# pc_heartypatch_v2.net
KiCad netlist of a schematic drawn in EAGLE
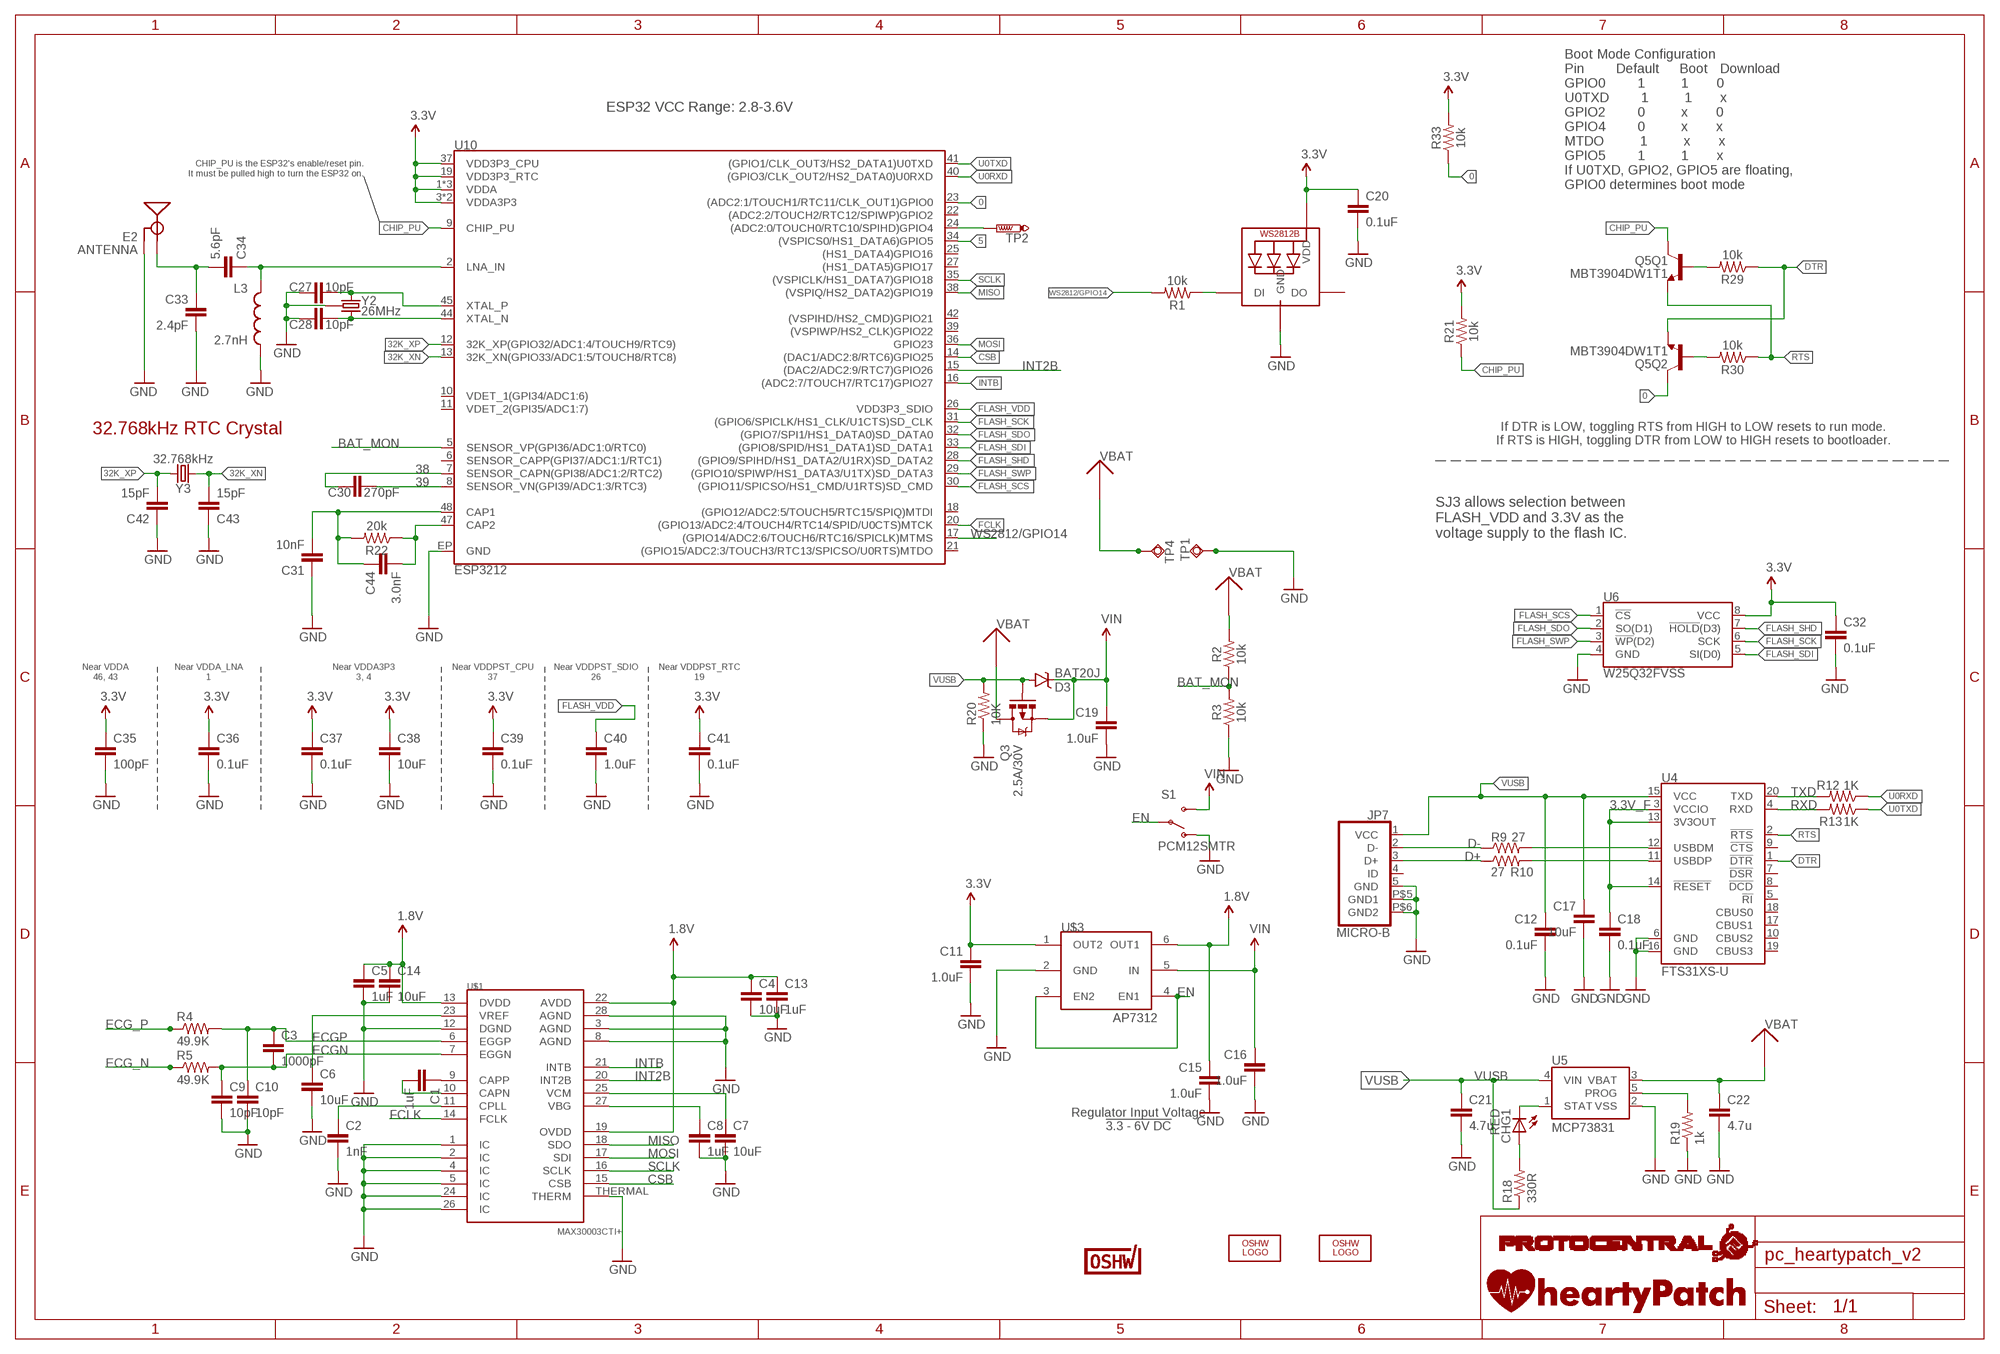
[diagram p0: schematic, sheet 1]

(export (version "E")
  (design (tool "Eeschema 10.0.6"))
  (components
    (comp (ref "C1")
      (value "1uF")
      (footprint "eagle-import:C0603")
      (libsource (lib "eagle-import") (part "C-EUC0603"))
    )
    (comp (ref "C2")
      (value "1nF")
      (footprint "eagle-import:C0603")
      (libsource (lib "eagle-import") (part "C-EUC0603"))
    )
    (comp (ref "C3")
      (value "1000pF")
      (footprint "eagle-import:C0402")
      (libsource (lib "eagle-import") (part "C-EUC0402"))
    )
    (comp (ref "C4")
      (value "10uF")
      (footprint "eagle-import:C0805")
      (libsource (lib "eagle-import") (part "C-EUC0805"))
    )
    (comp (ref "C5")
      (value "1uF")
      (footprint "eagle-import:C0402")
      (libsource (lib "eagle-import") (part "C-EUC0402"))
    )
    (comp (ref "C6")
      (value "10uF")
      (footprint "eagle-import:C0805")
      (libsource (lib "eagle-import") (part "C-EUC0805"))
    )
    (comp (ref "C7")
      (value "10uF")
      (footprint "eagle-import:C0805")
      (libsource (lib "eagle-import") (part "C-EUC0805"))
    )
    (comp (ref "C8")
      (value "1uF")
      (footprint "eagle-import:C0805")
      (libsource (lib "eagle-import") (part "C-EUC0805"))
    )
    (comp (ref "C9")
      (value "10pF")
      (footprint "eagle-import:C0402")
      (libsource (lib "eagle-import") (part "C-EUC0402"))
    )
    (comp (ref "C10")
      (value "10pF")
      (footprint "eagle-import:C0402")
      (libsource (lib "eagle-import") (part "C-EUC0402"))
    )
    (comp (ref "C11")
      (value "1.0uF")
      (footprint "eagle-import:0805")
      (libsource (lib "eagle-import") (part "1.0UF-0805-25V-10%"))
    )
    (comp (ref "C12")
      (value "0.1uF")
      (footprint "eagle-import:C0402")
      (libsource (lib "eagle-import") (part "C-EUC0402"))
    )
    (comp (ref "C13")
      (value "1uF")
      (footprint "eagle-import:C0805")
      (libsource (lib "eagle-import") (part "C-EUC0805"))
    )
    (comp (ref "C14")
      (value "10uF")
      (footprint "eagle-import:C0603")
      (libsource (lib "eagle-import") (part "C-EUC0603"))
    )
    (comp (ref "C15")
      (value "1.0uF")
      (footprint "eagle-import:0805")
      (libsource (lib "eagle-import") (part "1.0UF-0805-25V-10%"))
    )
    (comp (ref "C16")
      (value "1.0uF")
      (footprint "eagle-import:0805")
      (libsource (lib "eagle-import") (part "1.0UF-0805-25V-10%"))
    )
    (comp (ref "C17")
      (value "10uF")
      (footprint "eagle-import:C0805")
      (libsource (lib "eagle-import") (part "C-EUC0805"))
    )
    (comp (ref "C18")
      (value "0.1uF")
      (footprint "eagle-import:C0402")
      (libsource (lib "eagle-import") (part "C-EUC0402"))
    )
    (comp (ref "C19")
      (value "1.0uF")
      (footprint "eagle-import:C0402")
      (libsource (lib "eagle-import") (part "C-EUC0402"))
    )
    (comp (ref "C20")
      (value "0.1uF")
      (footprint "eagle-import:0603")
      (libsource (lib "eagle-import") (part "0.1UF-0603-25V-(+80/-20%)"))
    )
    (comp (ref "C21")
      (value "4.7u")
      (footprint "eagle-import:C0805")
      (libsource (lib "eagle-import") (part "C-EUC0805"))
    )
    (comp (ref "C22")
      (value "4.7u")
      (footprint "eagle-import:C0805")
      (libsource (lib "eagle-import") (part "C-EUC0805"))
    )
    (comp (ref "C27")
      (value "10pF")
      (footprint "eagle-import:0603")
      (libsource (lib "eagle-import") (part "10PF-0603-50V-5%"))
    )
    (comp (ref "C28")
      (value "10pF")
      (footprint "eagle-import:0603")
      (libsource (lib "eagle-import") (part "10PF-0603-50V-5%"))
    )
    (comp (ref "C30")
      (value "270pF")
      (footprint "eagle-import:0603")
      (libsource (lib "eagle-import") (part "270PF-50V-5%(0603)"))
    )
    (comp (ref "C31")
      (value "10nF")
      (footprint "eagle-import:0603")
      (libsource (lib "eagle-import") (part "10NF-0603-50V-10%"))
    )
    (comp (ref "C32")
      (value "0.1uF")
      (footprint "eagle-import:0402")
      (libsource (lib "eagle-import") (part "0.1UF-0402-16V-10%"))
    )
    (comp (ref "C33")
      (value "2.4pF")
      (footprint "eagle-import:0603")
      (libsource (lib "eagle-import") (part "2.4PF-0603-50V-5%"))
    )
    (comp (ref "C34")
      (value "5.6pF")
      (footprint "eagle-import:0603")
      (libsource (lib "eagle-import") (part "5.6PF-50V-5%(0603)"))
    )
    (comp (ref "C35")
      (value "100pF")
      (footprint "eagle-import:0603")
      (libsource (lib "eagle-import") (part "100PF-0603-50V-5%"))
    )
    (comp (ref "C36")
      (value "0.1uF")
      (footprint "eagle-import:0603")
      (libsource (lib "eagle-import") (part "0.1UF-0603-25V-(+80/-20%)"))
    )
    (comp (ref "C37")
      (value "0.1uF")
      (footprint "eagle-import:0603")
      (libsource (lib "eagle-import") (part "0.1UF-0603-25V-(+80/-20%)"))
    )
    (comp (ref "C38")
      (value "10uF")
      (footprint "eagle-import:0603")
      (libsource (lib "eagle-import") (part "10UF-0603-6.3V-20%"))
    )
    (comp (ref "C39")
      (value "0.1uF")
      (footprint "eagle-import:0402")
      (libsource (lib "eagle-import") (part "0.1UF-0402-16V-10%"))
    )
    (comp (ref "C40")
      (value "1.0uF")
      (footprint "eagle-import:0603")
      (libsource (lib "eagle-import") (part "1.0UF-0603-16V-10%"))
    )
    (comp (ref "C41")
      (value "0.1uF")
      (footprint "eagle-import:0603")
      (libsource (lib "eagle-import") (part "0.1UF-0603-25V-(+80/-20%)"))
    )
    (comp (ref "C42")
      (value "15pF")
      (footprint "eagle-import:0603")
      (libsource (lib "eagle-import") (part "15PF-0603-50V-5%"))
    )
    (comp (ref "C43")
      (value "15pF")
      (footprint "eagle-import:0603")
      (libsource (lib "eagle-import") (part "15PF-0603-50V-5%"))
    )
    (comp (ref "C44")
      (value "3.0nF")
      (footprint "eagle-import:0603")
      (libsource (lib "eagle-import") (part "3.0NF-0603-50V-5%"))
    )
    (comp (ref "CHG1")
      (value "RED")
      (footprint "eagle-import:CHIPLED_0603")
      (libsource (lib "eagle-import") (part "LEDCHIPLED_0603"))
    )
    (comp (ref "D3")
      (value "BAT20J")
      (footprint "eagle-import:SOD-323")
      (libsource (lib "eagle-import") (part "DIODE-SCHOTTKY-BAT20J"))
    )
    (comp (ref "E2")
      (value "ANTENNA")
      (footprint "eagle-import:TRACE_ANTENNA_2.4GHZ_25.7MM_TUNED")
      (libsource (lib "eagle-import") (part "ANTENNATRACE-TUNED"))
    )
    (comp (ref "JP7")
      (value "MICRO-B")
      (footprint "eagle-import:MICRO-B")
      (libsource (lib "eagle-import") (part "MICRO-B"))
    )
    (comp (ref "L3")
      (value "2.7nH")
      (footprint "eagle-import:0603")
      (libsource (lib "eagle-import") (part "INDUCTOR0603"))
    )
    (comp (ref "LED1")
      (value "WS2812B5050")
      (footprint "eagle-import:WS2812B")
      (libsource (lib "eagle-import") (part "WS2812B5050"))
    )
    (comp (ref "LOGO1")
      (value "OSHW_LOGO_FILLX0200-NT")
      (footprint "eagle-import:OSHW_FILLX200_NOTEXT")
      (libsource (lib "eagle-import") (part "OSHW_LOGO_FILLX0200-NT"))
    )
    (comp (ref "LOGO2")
      (value "OSHW_LOGO_FILLX0200-NT")
      (footprint "eagle-import:OSHW_FILLX200_NOTEXT")
      (libsource (lib "eagle-import") (part "OSHW_LOGO_FILLX0200-NT"))
    )
    (comp (ref "Q3")
      (value "2.5A/30V")
      (footprint "eagle-import:SOT23-3")
      (libsource (lib "eagle-import") (part "MOSFET-PCHANNELDMG2307L"))
    )
    (comp (ref "Q5")
      (value "MBT3904DW1T1")
      (footprint "eagle-import:SC70-6")
      (libsource (lib "eagle-import") (part "MBT3904DW1T1"))
    )
    (comp (ref "R1")
      (value "10k")
      (footprint "eagle-import:0603")
      (libsource (lib "eagle-import") (part "10KOHM-1/10W-1%(0603)0603"))
    )
    (comp (ref "R2")
      (value "10k")
      (footprint "eagle-import:0603")
      (libsource (lib "eagle-import") (part "10KOHM-1/10W-1%(0603)0603"))
    )
    (comp (ref "R3")
      (value "10k")
      (footprint "eagle-import:0603")
      (libsource (lib "eagle-import") (part "10KOHM-1/10W-1%(0603)0603"))
    )
    (comp (ref "R4")
      (value "49.9K")
      (footprint "eagle-import:0805")
      (libsource (lib "eagle-import") (part "RESISTOR0805-RES"))
    )
    (comp (ref "R5")
      (value "49.9K")
      (footprint "eagle-import:0805")
      (libsource (lib "eagle-import") (part "RESISTOR0805-RES"))
    )
    (comp (ref "R9")
      (value "27")
      (footprint "eagle-import:R0402")
      (libsource (lib "eagle-import") (part "R-US_R0402"))
    )
    (comp (ref "R10")
      (value "27")
      (footprint "eagle-import:R0402")
      (libsource (lib "eagle-import") (part "R-US_R0402"))
    )
    (comp (ref "R12")
      (value "1K")
      (footprint "eagle-import:R0402")
      (libsource (lib "eagle-import") (part "R-US_R0402"))
    )
    (comp (ref "R13")
      (value "1K")
      (footprint "eagle-import:R0402")
      (libsource (lib "eagle-import") (part "R-US_R0402"))
    )
    (comp (ref "R18")
      (value "330R")
      (footprint "eagle-import:R0402")
      (libsource (lib "eagle-import") (part "R-US_R0402"))
    )
    (comp (ref "R19")
      (value "1k")
      (footprint "eagle-import:R0402")
      (libsource (lib "eagle-import") (part "R-US_R0402"))
    )
    (comp (ref "R20")
      (value "10K")
      (footprint "eagle-import:R0402")
      (libsource (lib "eagle-import") (part "R-US_R0402"))
    )
    (comp (ref "R21")
      (value "10k")
      (footprint "eagle-import:0603")
      (libsource (lib "eagle-import") (part "10KOHM-1/10W-1%(0603)0603"))
    )
    (comp (ref "R22")
      (value "20k")
      (footprint "eagle-import:0603")
      (libsource (lib "eagle-import") (part "20KOHM-0603-1/10W-1%"))
    )
    (comp (ref "R29")
      (value "10k")
      (footprint "eagle-import:0603")
      (libsource (lib "eagle-import") (part "10KOHM-0603-1/10W-1%"))
    )
    (comp (ref "R30")
      (value "10k")
      (footprint "eagle-import:0603")
      (libsource (lib "eagle-import") (part "10KOHM-0603-1/10W-1%"))
    )
    (comp (ref "R33")
      (value "10k")
      (footprint "eagle-import:0603")
      (libsource (lib "eagle-import") (part "10KOHM-1/10W-1%(0603)0603"))
    )
    (comp (ref "S1")
      (value "PCM12SMTR")
      (footprint "eagle-import:SWITCH-SPST-SMD-A")
      (libsource (lib "eagle-import") (part "SWITCH-SPDT-SMD-A"))
    )
    (comp (ref "TP1")
      (value "TPSQTP20SQ")
      (footprint "eagle-import:TP20SQ")
      (libsource (lib "eagle-import") (part "TPSQTP20SQ"))
    )
    (comp (ref "TP2")
      (value "PTR1TP10SQ")
      (footprint "eagle-import:TP10SQ")
      (libsource (lib "eagle-import") (part "PTR1TP10SQ"))
    )
    (comp (ref "TP4")
      (value "TPSQTP20SQ")
      (footprint "eagle-import:TP20SQ")
      (libsource (lib "eagle-import") (part "TPSQTP20SQ"))
    )
    (comp (ref "U$1")
      (value "MAX30003CTI+")
      (footprint "eagle-import:QFN-28")
      (libsource (lib "eagle-import") (part "MAX30003"))
    )
    (comp (ref "U$3")
      (value "AP7312")
      (footprint "eagle-import:SOT26")
      (libsource (lib "eagle-import") (part "AP7312"))
    )
    (comp (ref "U$8")
      (value "HEARTYPATCHHEART")
      (footprint "eagle-import:HEARTYPATCH")
      (libsource (lib "eagle-import") (part "HEARTYPATCHHEART"))
    )
    (comp (ref "U$9")
      (value "PROTY_LOGO_WITH_TEXT")
      (footprint "eagle-import:PROTY_WITH_TEXT")
      (libsource (lib "eagle-import") (part "PROTY_LOGO_WITH_TEXT"))
    )
    (comp (ref "U$10")
      (value "CERT-SMALL")
      (footprint "eagle-import:CERT-SMALL-SILK")
      (libsource (lib "eagle-import") (part "CERT-SMALL"))
    )
    (comp (ref "U4")
      (value "FTS31XS-U")
      (footprint "eagle-import:SSOP20_L")
      (libsource (lib "eagle-import") (part "FT231XS"))
    )
    (comp (ref "U5")
      (value "MCP73831")
      (footprint "eagle-import:SOT23-5")
      (libsource (lib "eagle-import") (part "MCP73831"))
    )
    (comp (ref "U6")
      (value "W25Q32FVSS")
      (footprint "eagle-import:SOIC-8")
      (libsource (lib "eagle-import") (part "W25Q32FVSS"))
    )
    (comp (ref "U10")
      (value "ESP3212")
      (footprint "eagle-import:QFN48-0.4MM")
      (libsource (lib "eagle-import") (part "ESP3212"))
    )
    (comp (ref "Y2")
      (value "26MHz")
      (footprint "eagle-import:CRYSTAL-SMD-3.2X2.5")
      (libsource (lib "eagle-import") (part "CRYSTAL-GROUNDED3.2X2.5"))
    )
    (comp (ref "Y3")
      (value "32.768kHz")
      (footprint "eagle-import:CRYSTAL-SMD-3.2X1.5MM")
      (libsource (lib "eagle-import") (part "CRYSTAL-32.768KHZSMD-3.2X1.5"))
    )
  )
  (nets
    (net (code "1") (name "/3.3V_F") (class "Default")
      (node (ref "C18") (pin "1") (pinfunction "1_1") (pintype "passive"))
      (node (ref "U4") (pin "13") (pinfunction "3V3OUT_13") (pintype "bidirectional"))
      (node (ref "U4") (pin "14") (pinfunction "~{RESET}_14") (pintype "bidirectional"))
      (node (ref "U4") (pin "3") (pinfunction "VCCIO_3") (pintype "bidirectional"))
    )
    (net (code "2") (name "/38") (class "Default")
      (node (ref "C30") (pin "1") (pinfunction "1_1") (pintype "passive"))
      (node (ref "U10") (pin "7") (pinfunction "SENSOR_CAPN(GPI38/ADC1:2/RTC2)_7") (pintype "bidirectional"))
    )
    (net (code "3") (name "/39") (class "Default")
      (node (ref "C30") (pin "2") (pinfunction "2_2") (pintype "passive"))
      (node (ref "U10") (pin "8") (pinfunction "SENSOR_VN(GPI39/ADC1:3/RTC3)_8") (pintype "bidirectional"))
    )
    (net (code "4") (name "/BAT_MON") (class "Default")
      (node (ref "R2") (pin "1") (pinfunction "1_1") (pintype "passive"))
      (node (ref "R3") (pin "2") (pinfunction "2_2") (pintype "passive"))
      (node (ref "U10") (pin "5") (pinfunction "SENSOR_VP(GPI36/ADC1:0/RTC0)_5") (pintype "bidirectional"))
    )
    (net (code "5") (name "/D+") (class "Default")
      (node (ref "JP7") (pin "3") (pinfunction "D+_3") (pintype "bidirectional"))
      (node (ref "R10") (pin "1") (pinfunction "1_1") (pintype "passive"))
    )
    (net (code "6") (name "/D-") (class "Default")
      (node (ref "JP7") (pin "2") (pinfunction "D-_2") (pintype "bidirectional"))
      (node (ref "R9") (pin "1") (pinfunction "1_1") (pintype "passive"))
    )
    (net (code "7") (name "/ECGN") (class "Default")
      (node (ref "C3") (pin "2") (pinfunction "2_2") (pintype "passive"))
      (node (ref "C9") (pin "1") (pinfunction "1_1") (pintype "passive"))
      (node (ref "R5") (pin "2") (pinfunction "2_2") (pintype "passive"))
      (node (ref "U$1") (pin "7") (pinfunction "EGGN_7") (pintype "bidirectional"))
    )
    (net (code "8") (name "/ECGP") (class "Default")
      (node (ref "C10") (pin "1") (pinfunction "1_1") (pintype "passive"))
      (node (ref "C3") (pin "1") (pinfunction "1_1") (pintype "passive"))
      (node (ref "R4") (pin "2") (pinfunction "2_2") (pintype "passive"))
      (node (ref "U$1") (pin "6") (pinfunction "EGGP_6") (pintype "bidirectional"))
    )
    (net (code "9") (name "/ECG_N") (class "Default")
      (node (ref "R5") (pin "1") (pinfunction "1_1") (pintype "passive"))
    )
    (net (code "10") (name "/ECG_P") (class "Default")
      (node (ref "R4") (pin "1") (pinfunction "1_1") (pintype "passive"))
    )
    (net (code "11") (name "/EN") (class "Default")
      (node (ref "S1") (pin "2") (pinfunction "P_2") (pintype "passive"))
      (node (ref "U$3") (pin "3") (pinfunction "EN2_3") (pintype "bidirectional"))
      (node (ref "U$3") (pin "4") (pinfunction "EN1_4") (pintype "bidirectional"))
    )
    (net (code "12") (name "/INT2B") (class "Default")
      (node (ref "U$1") (pin "20") (pinfunction "INT2B_20") (pintype "bidirectional"))
      (node (ref "U10") (pin "15") (pinfunction "(DAC2/ADC2:9/RTC7)GPIO26_15") (pintype "bidirectional"))
    )
    (net (code "13") (name "/RXD") (class "Default")
      (node (ref "R13") (pin "2") (pinfunction "2_2") (pintype "passive"))
      (node (ref "U4") (pin "4") (pinfunction "RXD_4") (pintype "bidirectional"))
    )
    (net (code "14") (name "/TXD") (class "Default")
      (node (ref "R12") (pin "2") (pinfunction "2_2") (pintype "passive"))
      (node (ref "U4") (pin "20") (pinfunction "TXD_20") (pintype "bidirectional"))
    )
    (net (code "15") (name "0") (class "Default")
      (node (ref "Q5") (pin "6") (pinfunction "C_6") (pintype "passive"))
      (node (ref "R33") (pin "1") (pinfunction "1_1") (pintype "passive"))
      (node (ref "U10") (pin "23") (pinfunction "(ADC2:1/TOUCH1/RTC11/CLK_OUT1)GPIO0_23") (pintype "bidirectional"))
    )
    (net (code "16") (name "1.8V") (class "Default")
      (node (ref "C13") (pin "1") (pinfunction "1_1") (pintype "passive"))
      (node (ref "C14") (pin "1") (pinfunction "1_1") (pintype "passive"))
      (node (ref "C15") (pin "1") (pinfunction "1_1") (pintype "passive"))
      (node (ref "C4") (pin "1") (pinfunction "1_1") (pintype "passive"))
      (node (ref "C5") (pin "1") (pinfunction "1_1") (pintype "passive"))
      (node (ref "U$1") (pin "13") (pinfunction "DVDD_13") (pintype "bidirectional"))
      (node (ref "U$1") (pin "19") (pinfunction "OVDD_19") (pintype "bidirectional"))
      (node (ref "U$1") (pin "22") (pinfunction "AVDD_22") (pintype "bidirectional"))
      (node (ref "U$3") (pin "6") (pinfunction "OUT1_6") (pintype "bidirectional"))
    )
    (net (code "17") (name "3.3V") (class "Default")
      (node (ref "C11") (pin "1") (pinfunction "1_1") (pintype "passive"))
      (node (ref "C20") (pin "1") (pinfunction "1_1") (pintype "passive"))
      (node (ref "C32") (pin "1") (pinfunction "1_1") (pintype "passive"))
      (node (ref "C35") (pin "1") (pinfunction "1_1") (pintype "passive"))
      (node (ref "C36") (pin "1") (pinfunction "1_1") (pintype "passive"))
      (node (ref "C37") (pin "1") (pinfunction "1_1") (pintype "passive"))
      (node (ref "C38") (pin "1") (pinfunction "1_1") (pintype "passive"))
      (node (ref "C39") (pin "1") (pinfunction "1_1") (pintype "passive"))
      (node (ref "C41") (pin "1") (pinfunction "1_1") (pintype "passive"))
      (node (ref "LED1") (pin "1-VDD") (pinfunction "VDD_1-VDD") (pintype "power_in"))
      (node (ref "R21") (pin "2") (pinfunction "2_2") (pintype "passive"))
      (node (ref "R33") (pin "2") (pinfunction "2_2") (pintype "passive"))
      (node (ref "U$3") (pin "1") (pinfunction "OUT2_1") (pintype "bidirectional"))
      (node (ref "U10") (pin "1") (pinfunction "VDDA_1") (pintype "bidirectional"))
      (node (ref "U10") (pin "19") (pinfunction "VDD3P3_RTC_19") (pintype "bidirectional"))
      (node (ref "U10") (pin "3") (pinfunction "VDDA3P3_3") (pintype "bidirectional"))
      (node (ref "U10") (pin "37") (pinfunction "VDD3P3_CPU_37") (pintype "bidirectional"))
      (node (ref "U10") (pin "4") (pinfunction "VDDA3P3_4") (pintype "bidirectional"))
      (node (ref "U10") (pin "43") (pinfunction "VDDA_43") (pintype "bidirectional"))
      (node (ref "U10") (pin "46") (pinfunction "VDDA_46") (pintype "bidirectional"))
      (node (ref "U6") (pin "8") (pinfunction "VCC_8") (pintype "bidirectional"))
    )
    (net (code "18") (name "5") (class "Default")
      (node (ref "U10") (pin "34") (pinfunction "(VSPICS0/HS1_DATA6)GPIO5_34") (pintype "bidirectional"))
    )
    (net (code "19") (name "32K_XN") (class "Default")
      (node (ref "C43") (pin "2") (pinfunction "2_2") (pintype "passive"))
      (node (ref "U10") (pin "13") (pinfunction "32K_XN(GPIO33/ADC1:5/TOUCH8/RTC8)_13") (pintype "bidirectional"))
      (node (ref "Y3") (pin "P$2") (pinfunction "2_P$2") (pintype "passive"))
    )
    (net (code "20") (name "32K_XP") (class "Default")
      (node (ref "C42") (pin "2") (pinfunction "2_2") (pintype "passive"))
      (node (ref "U10") (pin "12") (pinfunction "32K_XP(GPIO32/ADC1:4/TOUCH9/RTC9)_12") (pintype "bidirectional"))
      (node (ref "Y3") (pin "P$1") (pinfunction "1_P$1") (pintype "passive"))
    )
    (net (code "21") (name "CHIP_PU") (class "Default")
      (node (ref "Q5") (pin "3") (pinfunction "C_3") (pintype "passive"))
      (node (ref "R21") (pin "1") (pinfunction "1_1") (pintype "passive"))
      (node (ref "U10") (pin "9") (pinfunction "CHIP_PU_9") (pintype "bidirectional"))
    )
    (net (code "22") (name "CSB") (class "Default")
      (node (ref "U$1") (pin "15") (pinfunction "CSB_15") (pintype "bidirectional"))
      (node (ref "U10") (pin "14") (pinfunction "(DAC1/ADC2:8/RTC6)GPIO25_14") (pintype "bidirectional"))
    )
    (net (code "23") (name "DTR") (class "Default")
      (node (ref "Q5") (pin "1") (pinfunction "E_1") (pintype "passive"))
      (node (ref "R29") (pin "1") (pinfunction "1_1") (pintype "passive"))
      (node (ref "U4") (pin "1") (pinfunction "~{DTR}_1") (pintype "bidirectional"))
    )
    (net (code "24") (name "FCLK") (class "Default")
      (node (ref "U$1") (pin "14") (pinfunction "FCLK_14") (pintype "bidirectional"))
      (node (ref "U10") (pin "20") (pinfunction "(GPIO13/ADC2:4/TOUCH4/RTC14/SPID/U0CTS)MTCK_20") (pintype "bidirectional"))
    )
    (net (code "25") (name "FLASH_SCK") (class "Default")
      (node (ref "U10") (pin "31") (pinfunction "(GPIO6/SPICLK/HS1_CLK/U1CTS)SD_CLK_31") (pintype "bidirectional"))
      (node (ref "U6") (pin "6") (pinfunction "SCK_6") (pintype "bidirectional"))
    )
    (net (code "26") (name "FLASH_SCS") (class "Default")
      (node (ref "U10") (pin "30") (pinfunction "(GPIO11/SPICSO/HS1_CMD/U1RTS)SD_CMD_30") (pintype "bidirectional"))
      (node (ref "U6") (pin "1") (pinfunction "~{CS}_1") (pintype "bidirectional"))
    )
    (net (code "27") (name "FLASH_SDI") (class "Default")
      (node (ref "U10") (pin "33") (pinfunction "(GPIO8/SPID/HS1_DATA1)SD_DATA1_33") (pintype "bidirectional"))
      (node (ref "U6") (pin "5") (pinfunction "SI(D0)_5") (pintype "bidirectional"))
    )
    (net (code "28") (name "FLASH_SDO") (class "Default")
      (node (ref "U10") (pin "32") (pinfunction "(GPIO7/SPI1/HS1_DATA0)SD_DATA0_32") (pintype "bidirectional"))
      (node (ref "U6") (pin "2") (pinfunction "SO(D1)_2") (pintype "bidirectional"))
    )
    (net (code "29") (name "FLASH_SHD") (class "Default")
      (node (ref "U10") (pin "28") (pinfunction "(GPIO9/SPIHD/HS1_DATA2/U1RX)SD_DATA2_28") (pintype "bidirectional"))
      (node (ref "U6") (pin "7") (pinfunction "~{HOLD}(D3)_7") (pintype "bidirectional"))
    )
    (net (code "30") (name "FLASH_SWP") (class "Default")
      (node (ref "U10") (pin "29") (pinfunction "(GPIO10/SPIWP/HS1_DATA3/U1TX)SD_DATA3_29") (pintype "bidirectional"))
      (node (ref "U6") (pin "3") (pinfunction "~{WP}(D2)_3") (pintype "bidirectional"))
    )
    (net (code "31") (name "FLASH_VDD") (class "Default")
      (node (ref "C40") (pin "1") (pinfunction "1_1") (pintype "passive"))
      (node (ref "U10") (pin "26") (pinfunction "VDD3P3_SDIO_26") (pintype "bidirectional"))
    )
    (net (code "32") (name "GND") (class "Default")
      (node (ref "C10") (pin "2") (pinfunction "2_2") (pintype "passive"))
      (node (ref "C11") (pin "2") (pinfunction "2_2") (pintype "passive"))
      (node (ref "C12") (pin "2") (pinfunction "2_2") (pintype "passive"))
      (node (ref "C13") (pin "2") (pinfunction "2_2") (pintype "passive"))
      (node (ref "C14") (pin "2") (pinfunction "2_2") (pintype "passive"))
      (node (ref "C15") (pin "2") (pinfunction "2_2") (pintype "passive"))
      (node (ref "C16") (pin "2") (pinfunction "2_2") (pintype "passive"))
      (node (ref "C17") (pin "2") (pinfunction "2_2") (pintype "passive"))
      (node (ref "C18") (pin "2") (pinfunction "2_2") (pintype "passive"))
      (node (ref "C19") (pin "2") (pinfunction "2_2") (pintype "passive"))
      (node (ref "C2") (pin "2") (pinfunction "2_2") (pintype "passive"))
      (node (ref "C20") (pin "2") (pinfunction "2_2") (pintype "passive"))
      (node (ref "C21") (pin "2") (pinfunction "2_2") (pintype "passive"))
      (node (ref "C22") (pin "2") (pinfunction "2_2") (pintype "passive"))
      (node (ref "C27") (pin "1") (pinfunction "1_1") (pintype "passive"))
      (node (ref "C28") (pin "1") (pinfunction "1_1") (pintype "passive"))
      (node (ref "C31") (pin "1") (pinfunction "1_1") (pintype "passive"))
      (node (ref "C32") (pin "2") (pinfunction "2_2") (pintype "passive"))
      (node (ref "C33") (pin "2") (pinfunction "2_2") (pintype "passive"))
      (node (ref "C35") (pin "2") (pinfunction "2_2") (pintype "passive"))
      (node (ref "C36") (pin "2") (pinfunction "2_2") (pintype "passive"))
      (node (ref "C37") (pin "2") (pinfunction "2_2") (pintype "passive"))
      (node (ref "C38") (pin "2") (pinfunction "2_2") (pintype "passive"))
      (node (ref "C39") (pin "2") (pinfunction "2_2") (pintype "passive"))
      (node (ref "C4") (pin "2") (pinfunction "2_2") (pintype "passive"))
      (node (ref "C40") (pin "2") (pinfunction "2_2") (pintype "passive"))
      (node (ref "C41") (pin "2") (pinfunction "2_2") (pintype "passive"))
      (node (ref "C42") (pin "1") (pinfunction "1_1") (pintype "passive"))
      (node (ref "C43") (pin "1") (pinfunction "1_1") (pintype "passive"))
      (node (ref "C5") (pin "2") (pinfunction "2_2") (pintype "passive"))
      (node (ref "C6") (pin "2") (pinfunction "2_2") (pintype "passive"))
      (node (ref "C7") (pin "2") (pinfunction "2_2") (pintype "passive"))
      (node (ref "C8") (pin "2") (pinfunction "2_2") (pintype "passive"))
      (node (ref "C9") (pin "2") (pinfunction "2_2") (pintype "passive"))
      (node (ref "E2") (pin "GND") (pinfunction "GND_GND") (pintype "bidirectional"))
      (node (ref "E2") (pin "GND2") (pinfunction "GND_GND2") (pintype "bidirectional"))
      (node (ref "JP7") (pin "5") (pinfunction "GND_5") (pintype "bidirectional"))
      (node (ref "JP7") (pin "P$5") (pinfunction "GND1_P$5") (pintype "bidirectional"))
      (node (ref "JP7") (pin "P$6") (pinfunction "GND2_P$6") (pintype "bidirectional"))
      (node (ref "L3") (pin "2") (pinfunction "2_2") (pintype "passive"))
      (node (ref "LED1") (pin "3-GND") (pinfunction "GND_3-GND") (pintype "power_in"))
      (node (ref "R19") (pin "1") (pinfunction "1_1") (pintype "passive"))
      (node (ref "R20") (pin "1") (pinfunction "1_1") (pintype "passive"))
      (node (ref "R3") (pin "1") (pinfunction "1_1") (pintype "passive"))
      (node (ref "S1") (pin "1") (pinfunction "O_1") (pintype "passive"))
      (node (ref "TP1") (pin "TP") (pinfunction "TP_TP") (pintype "input"))
      (node (ref "U$1") (pin "1") (pinfunction "IC_1") (pintype "bidirectional"))
      (node (ref "U$1") (pin "12") (pinfunction "DGND_12") (pintype "bidirectional"))
      (node (ref "U$1") (pin "2") (pinfunction "IC_2") (pintype "bidirectional"))
      (node (ref "U$1") (pin "24") (pinfunction "IC_24") (pintype "bidirectional"))
      (node (ref "U$1") (pin "26") (pinfunction "IC_26") (pintype "bidirectional"))
      (node (ref "U$1") (pin "28") (pinfunction "AGND_28") (pintype "bidirectional"))
      (node (ref "U$1") (pin "3") (pinfunction "AGND_3") (pintype "bidirectional"))
      (node (ref "U$1") (pin "4") (pinfunction "IC_4") (pintype "bidirectional"))
      (node (ref "U$1") (pin "5") (pinfunction "IC_5") (pintype "bidirectional"))
      (node (ref "U$1") (pin "8") (pinfunction "AGND_8") (pintype "bidirectional"))
      (node (ref "U$1") (pin "THERMAL") (pinfunction "THERM_THERMAL") (pintype "bidirectional"))
      (node (ref "U$3") (pin "2") (pinfunction "GND_2") (pintype "bidirectional"))
      (node (ref "U10") (pin "EP") (pinfunction "GND_EP") (pintype "bidirectional"))
      (node (ref "U4") (pin "16") (pinfunction "GND_16") (pintype "bidirectional"))
      (node (ref "U4") (pin "6") (pinfunction "GND_6") (pintype "bidirectional"))
      (node (ref "U5") (pin "2") (pinfunction "VSS_2") (pintype "power_in"))
      (node (ref "U6") (pin "4") (pinfunction "GND_4") (pintype "bidirectional"))
      (node (ref "Y2") (pin "2") (pinfunction "GND_2") (pintype "passive"))
      (node (ref "Y2") (pin "4") (pinfunction "GND_4") (pintype "passive"))
    )
    (net (code "33") (name "INTB") (class "Default")
      (node (ref "U$1") (pin "21") (pinfunction "INTB_21") (pintype "bidirectional"))
      (node (ref "U10") (pin "16") (pinfunction "(ADC2:7/TOUCH7/RTC17)GPIO27_16") (pintype "bidirectional"))
    )
    (net (code "34") (name "MISO") (class "Default")
      (node (ref "U$1") (pin "18") (pinfunction "SDO_18") (pintype "bidirectional"))
      (node (ref "U10") (pin "38") (pinfunction "(VSPIQ/HS2_DATA2)GPIO19_38") (pintype "bidirectional"))
    )
    (net (code "35") (name "MOSI") (class "Default")
      (node (ref "U$1") (pin "17") (pinfunction "SDI_17") (pintype "bidirectional"))
      (node (ref "U10") (pin "36") (pinfunction "GPIO23_36") (pintype "bidirectional"))
    )
    (net (code "36") (name "Net-(CHG1-PadA)") (class "Default")
      (node (ref "CHG1") (pin "A") (pinfunction "A_A") (pintype "passive"))
      (node (ref "R18") (pin "2") (pinfunction "2_2") (pintype "passive"))
    )
    (net (code "37") (name "Net-(E2-SIGNAL)") (class "Default")
      (node (ref "C33") (pin "1") (pinfunction "1_1") (pintype "passive"))
      (node (ref "C34") (pin "2") (pinfunction "2_2") (pintype "passive"))
      (node (ref "E2") (pin "ANT") (pinfunction "SIGNAL_ANT") (pintype "bidirectional"))
    )
    (net (code "38") (name "Net-(LED1-DI)") (class "Default")
      (node (ref "LED1") (pin "4-DIN") (pinfunction "DI_4-DIN") (pintype "input"))
      (node (ref "R1") (pin "1") (pinfunction "1_1") (pintype "passive"))
    )
    (net (code "39") (name "Net-(Q5A-B)") (class "Default")
      (node (ref "Q5") (pin "5") (pinfunction "B_5") (pintype "passive"))
      (node (ref "R29") (pin "2") (pinfunction "2_2") (pintype "passive"))
    )
    (net (code "40") (name "Net-(Q5B-B)") (class "Default")
      (node (ref "Q5") (pin "2") (pinfunction "B_2") (pintype "passive"))
      (node (ref "R30") (pin "2") (pinfunction "2_2") (pintype "passive"))
    )
    (net (code "41") (name "Net-(U$1-CAPN)") (class "Default")
      (node (ref "C1") (pin "2") (pinfunction "2_2") (pintype "passive"))
      (node (ref "U$1") (pin "10") (pinfunction "CAPN_10") (pintype "bidirectional"))
    )
    (net (code "42") (name "Net-(U$1-CAPP)") (class "Default")
      (node (ref "C1") (pin "1") (pinfunction "1_1") (pintype "passive"))
      (node (ref "U$1") (pin "9") (pinfunction "CAPP_9") (pintype "bidirectional"))
    )
    (net (code "43") (name "Net-(U$1-CPLL)") (class "Default")
      (node (ref "C2") (pin "1") (pinfunction "1_1") (pintype "passive"))
      (node (ref "U$1") (pin "11") (pinfunction "CPLL_11") (pintype "bidirectional"))
    )
    (net (code "44") (name "Net-(U$1-VBG)") (class "Default")
      (node (ref "C8") (pin "1") (pinfunction "1_1") (pintype "passive"))
      (node (ref "U$1") (pin "27") (pinfunction "VBG_27") (pintype "bidirectional"))
    )
    (net (code "45") (name "Net-(U$1-VCM)") (class "Default")
      (node (ref "C7") (pin "1") (pinfunction "1_1") (pintype "passive"))
      (node (ref "U$1") (pin "25") (pinfunction "VCM_25") (pintype "bidirectional"))
    )
    (net (code "46") (name "Net-(U$1-VREF)") (class "Default")
      (node (ref "C6") (pin "1") (pinfunction "1_1") (pintype "passive"))
      (node (ref "U$1") (pin "23") (pinfunction "VREF_23") (pintype "bidirectional"))
    )
    (net (code "47") (name "Net-(U4-USBDM)") (class "Default")
      (node (ref "R9") (pin "2") (pinfunction "2_2") (pintype "passive"))
      (node (ref "U4") (pin "12") (pinfunction "USBDM_12") (pintype "bidirectional"))
    )
    (net (code "48") (name "Net-(U4-USBDP)") (class "Default")
      (node (ref "R10") (pin "2") (pinfunction "2_2") (pintype "passive"))
      (node (ref "U4") (pin "11") (pinfunction "USBDP_11") (pintype "bidirectional"))
    )
    (net (code "49") (name "Net-(U5-PROG)") (class "Default")
      (node (ref "R19") (pin "2") (pinfunction "2_2") (pintype "passive"))
      (node (ref "U5") (pin "5") (pinfunction "PROG_5") (pintype "input"))
    )
    (net (code "50") (name "Net-(U5-STAT)") (class "Default")
      (node (ref "CHG1") (pin "C") (pinfunction "C_C") (pintype "passive"))
      (node (ref "U5") (pin "1") (pinfunction "STAT_1") (pintype "output"))
    )
    (net (code "51") (name "Net-(U10-(ADC2:0{slash}TOUCH0{slash}RTC10{slash}SPIHD)GPIO4)") (class "Default")
      (node (ref "TP2") (pin "TP") (pinfunction "TP_TP") (pintype "input"))
      (node (ref "U10") (pin "24") (pinfunction "(ADC2:0/TOUCH0/RTC10/SPIHD)GPIO4_24") (pintype "bidirectional"))
    )
    (net (code "52") (name "Net-(U10-CAP1)") (class "Default")
      (node (ref "C31") (pin "2") (pinfunction "2_2") (pintype "passive"))
      (node (ref "C44") (pin "1") (pinfunction "1_1") (pintype "passive"))
      (node (ref "R22") (pin "2") (pinfunction "2_2") (pintype "passive"))
      (node (ref "U10") (pin "48") (pinfunction "CAP1_48") (pintype "bidirectional"))
    )
    (net (code "53") (name "Net-(U10-CAP2)") (class "Default")
      (node (ref "C44") (pin "2") (pinfunction "2_2") (pintype "passive"))
      (node (ref "R22") (pin "1") (pinfunction "1_1") (pintype "passive"))
      (node (ref "U10") (pin "47") (pinfunction "CAP2_47") (pintype "bidirectional"))
    )
    (net (code "54") (name "Net-(U10-LNA_IN)") (class "Default")
      (node (ref "C34") (pin "1") (pinfunction "1_1") (pintype "passive"))
      (node (ref "L3") (pin "1") (pinfunction "1_1") (pintype "passive"))
      (node (ref "U10") (pin "2") (pinfunction "LNA_IN_2") (pintype "bidirectional"))
    )
    (net (code "55") (name "Net-(U10-XTAL_N)") (class "Default")
      (node (ref "C28") (pin "2") (pinfunction "2_2") (pintype "passive"))
      (node (ref "U10") (pin "44") (pinfunction "XTAL_N_44") (pintype "bidirectional"))
      (node (ref "Y2") (pin "3") (pinfunction "2_3") (pintype "passive"))
    )
    (net (code "56") (name "Net-(U10-XTAL_P)") (class "Default")
      (node (ref "C27") (pin "2") (pinfunction "2_2") (pintype "passive"))
      (node (ref "U10") (pin "45") (pinfunction "XTAL_P_45") (pintype "bidirectional"))
      (node (ref "Y2") (pin "1") (pinfunction "1_1") (pintype "passive"))
    )
    (net (code "57") (name "RTS") (class "Default")
      (node (ref "Q5") (pin "4") (pinfunction "E_4") (pintype "passive"))
      (node (ref "R30") (pin "1") (pinfunction "1_1") (pintype "passive"))
      (node (ref "U4") (pin "2") (pinfunction "~{RTS}_2") (pintype "bidirectional"))
    )
    (net (code "58") (name "SCLK") (class "Default")
      (node (ref "U$1") (pin "16") (pinfunction "SCLK_16") (pintype "bidirectional"))
      (node (ref "U10") (pin "35") (pinfunction "(VSPICLK/HS1_DATA7)GPIO18_35") (pintype "bidirectional"))
    )
    (net (code "59") (name "U0RXD") (class "Default")
      (node (ref "R12") (pin "1") (pinfunction "1_1") (pintype "passive"))
      (node (ref "U10") (pin "40") (pinfunction "(GPIO3/CLK_OUT2/HS2_DATA0)U0RXD_40") (pintype "bidirectional"))
    )
    (net (code "60") (name "U0TXD") (class "Default")
      (node (ref "R13") (pin "1") (pinfunction "1_1") (pintype "passive"))
      (node (ref "U10") (pin "41") (pinfunction "(GPIO1/CLK_OUT3/HS2_DATA1)U0TXD_41") (pintype "bidirectional"))
    )
    (net (code "61") (name "VBAT") (class "Default")
      (node (ref "C22") (pin "1") (pinfunction "1_1") (pintype "passive"))
      (node (ref "Q3") (pin "3") (pinfunction "D_3") (pintype "passive"))
      (node (ref "R2") (pin "2") (pinfunction "2_2") (pintype "passive"))
      (node (ref "TP4") (pin "TP") (pinfunction "TP_TP") (pintype "input"))
      (node (ref "U5") (pin "3") (pinfunction "VBAT_3") (pintype "power_in"))
    )
    (net (code "62") (name "VIN") (class "Default")
      (node (ref "C16") (pin "1") (pinfunction "1_1") (pintype "passive"))
      (node (ref "C19") (pin "1") (pinfunction "1_1") (pintype "passive"))
      (node (ref "D3") (pin "C") (pinfunction "C_C") (pintype "passive"))
      (node (ref "Q3") (pin "2") (pinfunction "S_2") (pintype "passive"))
      (node (ref "S1") (pin "3") (pinfunction "S_3") (pintype "passive"))
      (node (ref "U$3") (pin "5") (pinfunction "IN_5") (pintype "bidirectional"))
    )
    (net (code "63") (name "VUSB") (class "Default")
      (node (ref "C12") (pin "1") (pinfunction "1_1") (pintype "passive"))
      (node (ref "C17") (pin "1") (pinfunction "1_1") (pintype "passive"))
      (node (ref "C21") (pin "1") (pinfunction "1_1") (pintype "passive"))
      (node (ref "D3") (pin "A") (pinfunction "A_A") (pintype "passive"))
      (node (ref "JP7") (pin "1") (pinfunction "VCC_1") (pintype "bidirectional"))
      (node (ref "Q3") (pin "1") (pinfunction "G_1") (pintype "passive"))
      (node (ref "R18") (pin "1") (pinfunction "1_1") (pintype "passive"))
      (node (ref "R20") (pin "2") (pinfunction "2_2") (pintype "passive"))
      (node (ref "U4") (pin "15") (pinfunction "VCC_15") (pintype "bidirectional"))
      (node (ref "U5") (pin "4") (pinfunction "VIN_4") (pintype "power_in"))
    )
    (net (code "64") (name "WS2812{slash}GPIO14") (class "Default")
      (node (ref "R1") (pin "2") (pinfunction "2_2") (pintype "passive"))
      (node (ref "U10") (pin "17") (pinfunction "(GPIO14/ADC2:6/TOUCH6/RTC16/SPICLK)MTMS_17") (pintype "bidirectional"))
    )
    (net (code "65") (name "unconnected-(JP7-ID-Pad4)") (class "Default")
      (node (ref "JP7") (pin "4") (pinfunction "ID_4") (pintype "bidirectional"))
    )
    (net (code "66") (name "unconnected-(LED1-DO-Pad2-DOUT)") (class "Default")
      (node (ref "LED1") (pin "2-DOUT") (pinfunction "DO_2-DOUT") (pintype "output"))
    )
    (net (code "67") (name "unconnected-(U4-CBUS0-Pad18)") (class "Default")
      (node (ref "U4") (pin "18") (pinfunction "CBUS0_18") (pintype "bidirectional"))
    )
    (net (code "68") (name "unconnected-(U4-CBUS1-Pad17)") (class "Default")
      (node (ref "U4") (pin "17") (pinfunction "CBUS1_17") (pintype "bidirectional"))
    )
    (net (code "69") (name "unconnected-(U4-CBUS2-Pad10)") (class "Default")
      (node (ref "U4") (pin "10") (pinfunction "CBUS2_10") (pintype "bidirectional"))
    )
    (net (code "70") (name "unconnected-(U4-CBUS3-Pad19)") (class "Default")
      (node (ref "U4") (pin "19") (pinfunction "CBUS3_19") (pintype "bidirectional"))
    )
    (net (code "71") (name "unconnected-(U4-~{CTS}-Pad9)") (class "Default")
      (node (ref "U4") (pin "9") (pinfunction "~{CTS}_9") (pintype "bidirectional"))
    )
    (net (code "72") (name "unconnected-(U4-~{DCD}-Pad8)") (class "Default")
      (node (ref "U4") (pin "8") (pinfunction "~{DCD}_8") (pintype "bidirectional"))
    )
    (net (code "73") (name "unconnected-(U4-~{DSR}-Pad7)") (class "Default")
      (node (ref "U4") (pin "7") (pinfunction "~{DSR}_7") (pintype "bidirectional"))
    )
    (net (code "74") (name "unconnected-(U4-~{RI}-Pad5)") (class "Default")
      (node (ref "U4") (pin "5") (pinfunction "~{RI}_5") (pintype "bidirectional"))
    )
    (net (code "75") (name "unconnected-(U10-(ADC2:2{slash}TOUCH2{slash}RTC12{slash}SPIWP)GPIO2-Pad22)") (class "Default")
      (node (ref "U10") (pin "22") (pinfunction "(ADC2:2/TOUCH2/RTC12/SPIWP)GPIO2_22") (pintype "bidirectional"))
    )
    (net (code "76") (name "unconnected-(U10-(GPIO12{slash}ADC2:5{slash}TOUCH5{slash}RTC15{slash}SPIQ)MTDI-Pad18)") (class "Default")
      (node (ref "U10") (pin "18") (pinfunction "(GPIO12/ADC2:5/TOUCH5/RTC15/SPIQ)MTDI_18") (pintype "bidirectional"))
    )
    (net (code "77") (name "unconnected-(U10-(GPIO15{slash}ADC2:3{slash}TOUCH3{slash}RTC13{slash}SPICSO{slash}U0RTS)MTDO-Pad21)") (class "Default")
      (node (ref "U10") (pin "21") (pinfunction "(GPIO15/ADC2:3/TOUCH3/RTC13/SPICSO/U0RTS)MTDO_21") (pintype "bidirectional"))
    )
    (net (code "78") (name "unconnected-(U10-(HS1_DATA4)GPIO16-Pad25)") (class "Default")
      (node (ref "U10") (pin "25") (pinfunction "(HS1_DATA4)GPIO16_25") (pintype "bidirectional"))
    )
    (net (code "79") (name "unconnected-(U10-(HS1_DATA5)GPIO17-Pad27)") (class "Default")
      (node (ref "U10") (pin "27") (pinfunction "(HS1_DATA5)GPIO17_27") (pintype "bidirectional"))
    )
    (net (code "80") (name "unconnected-(U10-(VSPIHD{slash}HS2_CMD)GPIO21-Pad42)") (class "Default")
      (node (ref "U10") (pin "42") (pinfunction "(VSPIHD/HS2_CMD)GPIO21_42") (pintype "bidirectional"))
    )
    (net (code "81") (name "unconnected-(U10-(VSPIWP{slash}HS2_CLK)GPIO22-Pad39)") (class "Default")
      (node (ref "U10") (pin "39") (pinfunction "(VSPIWP/HS2_CLK)GPIO22_39") (pintype "bidirectional"))
    )
    (net (code "82") (name "unconnected-(U10-SENSOR_CAPP(GPI37{slash}ADC1:1{slash}RTC1)-Pad6)") (class "Default")
      (node (ref "U10") (pin "6") (pinfunction "SENSOR_CAPP(GPI37/ADC1:1/RTC1)_6") (pintype "bidirectional"))
    )
    (net (code "83") (name "unconnected-(U10-VDET_1(GPI34{slash}ADC1:6)-Pad10)") (class "Default")
      (node (ref "U10") (pin "10") (pinfunction "VDET_1(GPI34/ADC1:6)_10") (pintype "bidirectional"))
    )
    (net (code "84") (name "unconnected-(U10-VDET_2(GPI35{slash}ADC1:7)-Pad11)") (class "Default")
      (node (ref "U10") (pin "11") (pinfunction "VDET_2(GPI35/ADC1:7)_11") (pintype "bidirectional"))
    )
  )
)
